# micromouse2019_enc.net
KiCad netlist of a schematic drawn in EAGLE
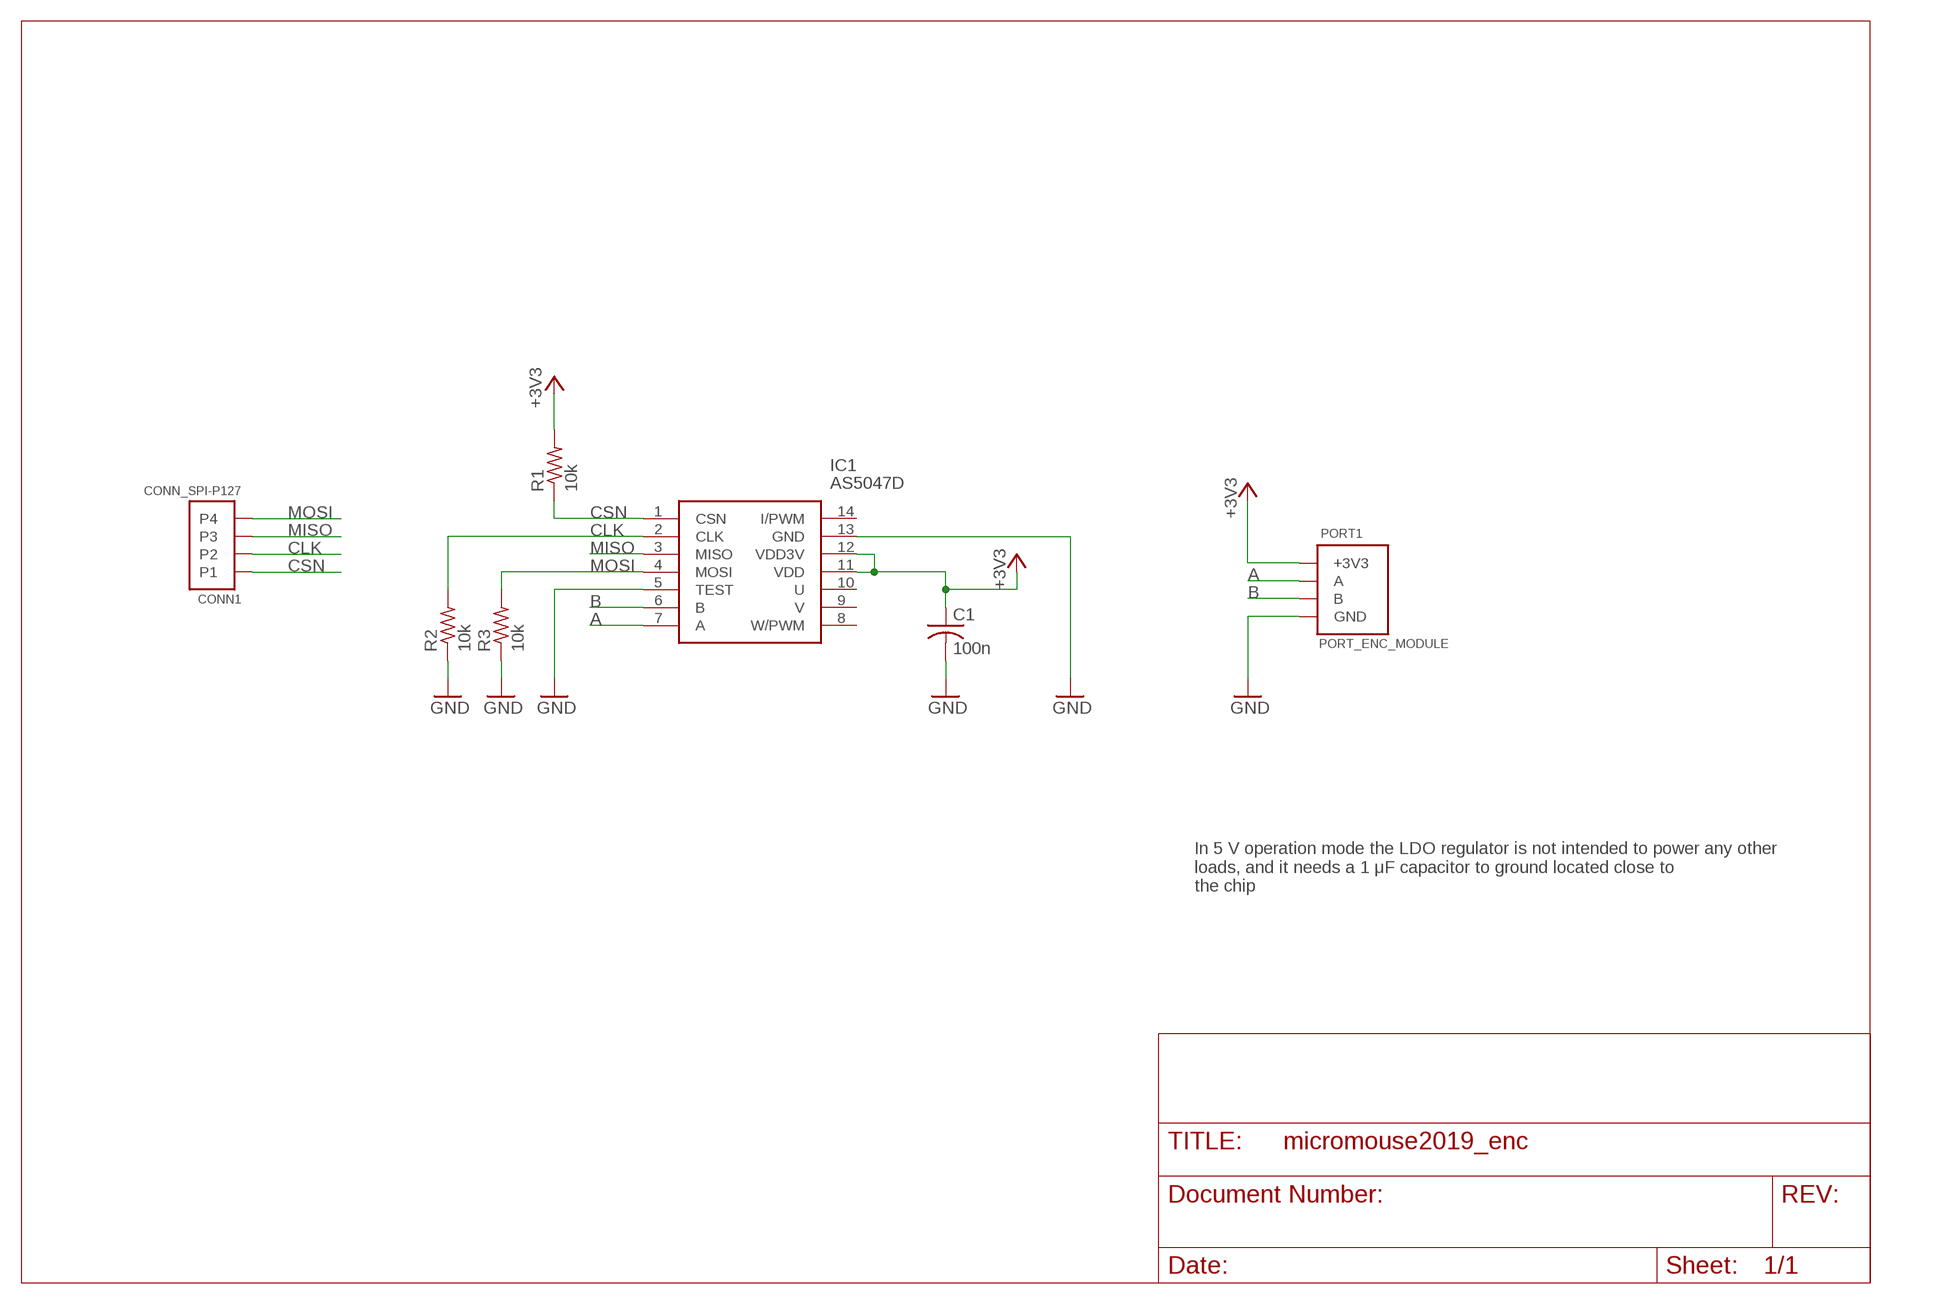
[diagram p0: schematic, sheet 1]

(export (version "E")
  (design (tool "Eeschema 10.0.6"))
  (components
    (comp (ref "C1")
      (value "100n")
      (footprint "eagle-import:C0402")
      (libsource (lib "eagle-import") (part "C-USC0402"))
    )
    (comp (ref "CONN1")
      (value "CONN_SPI-P127")
      (footprint "eagle-import:CONN_SPI_HDRRA4W40P127_1X4_549X220X220B")
      (libsource (lib "eagle-import") (part "CONN_SPI-P127"))
    )
    (comp (ref "IC1")
      (value "AS5047D")
      (footprint "eagle-import:SOP65P640X120-14N")
      (fields
        (field (name "MANUFACTURER_PART_NUMBER") "AS5047D-ATSM")
        (field (name "MOUSER_PART_NUMBER") "985-AS5047D-ATSM")
        (field (name "RS_PART_NUMBER") "1700756")
      )
      (libsource (lib "eagle-import") (part "AS5047D-ATSM"))
    )
    (comp (ref "PORT1")
      (value "PORT_ENC_MODULE")
      (footprint "eagle-import:ENC_PORT_MODULE")
      (libsource (lib "eagle-import") (part "PORT_ENC_MODULE"))
    )
    (comp (ref "R1")
      (value "10k")
      (footprint "eagle-import:R0402")
      (libsource (lib "eagle-import") (part "R-US_R0402"))
    )
    (comp (ref "R2")
      (value "10k")
      (footprint "eagle-import:R0402")
      (libsource (lib "eagle-import") (part "R-US_R0402"))
    )
    (comp (ref "R3")
      (value "10k")
      (footprint "eagle-import:R0402")
      (libsource (lib "eagle-import") (part "R-US_R0402"))
    )
  )
  (nets
    (net (code "1") (name "+3V3") (class "Default")
      (node (ref "C1") (pin "1") (pinfunction "1_1") (pintype "passive"))
      (node (ref "IC1") (pin "11") (pinfunction "VDD_11") (pintype "bidirectional"))
      (node (ref "IC1") (pin "12") (pinfunction "VDD3V_12") (pintype "bidirectional"))
      (node (ref "PORT1") (pin "P3") (pinfunction "+3V3_P3") (pintype "power_in"))
      (node (ref "R1") (pin "2") (pinfunction "2_2") (pintype "passive"))
    )
    (net (code "2") (name "/A") (class "Default")
      (node (ref "IC1") (pin "7") (pinfunction "A_7") (pintype "bidirectional"))
      (node (ref "PORT1") (pin "P1") (pinfunction "A_P1") (pintype "output"))
    )
    (net (code "3") (name "/B") (class "Default")
      (node (ref "IC1") (pin "6") (pinfunction "B_6") (pintype "bidirectional"))
      (node (ref "PORT1") (pin "P2") (pinfunction "B_P2") (pintype "output"))
    )
    (net (code "4") (name "/CLK") (class "Default")
      (node (ref "CONN1") (pin "2") (pinfunction "P2_2") (pintype "bidirectional"))
      (node (ref "IC1") (pin "2") (pinfunction "CLK_2") (pintype "bidirectional"))
      (node (ref "R2") (pin "2") (pinfunction "2_2") (pintype "passive"))
    )
    (net (code "5") (name "/CSN") (class "Default")
      (node (ref "CONN1") (pin "1") (pinfunction "P1_1") (pintype "bidirectional"))
      (node (ref "IC1") (pin "1") (pinfunction "CSN_1") (pintype "bidirectional"))
      (node (ref "R1") (pin "1") (pinfunction "1_1") (pintype "passive"))
    )
    (net (code "6") (name "/MISO") (class "Default")
      (node (ref "CONN1") (pin "3") (pinfunction "P3_3") (pintype "bidirectional"))
      (node (ref "IC1") (pin "3") (pinfunction "MISO_3") (pintype "bidirectional"))
    )
    (net (code "7") (name "/MOSI") (class "Default")
      (node (ref "CONN1") (pin "4") (pinfunction "P4_4") (pintype "bidirectional"))
      (node (ref "IC1") (pin "4") (pinfunction "MOSI_4") (pintype "bidirectional"))
      (node (ref "R3") (pin "2") (pinfunction "2_2") (pintype "passive"))
    )
    (net (code "8") (name "GND") (class "Default")
      (node (ref "C1") (pin "2") (pinfunction "2_2") (pintype "passive"))
      (node (ref "IC1") (pin "13") (pinfunction "GND_13") (pintype "bidirectional"))
      (node (ref "IC1") (pin "5") (pinfunction "TEST_5") (pintype "bidirectional"))
      (node (ref "PORT1") (pin "P4") (pinfunction "GND_P4") (pintype "passive"))
      (node (ref "R2") (pin "1") (pinfunction "1_1") (pintype "passive"))
      (node (ref "R3") (pin "1") (pinfunction "1_1") (pintype "passive"))
    )
    (net (code "9") (name "unconnected-(IC1-I{slash}PWM-Pad14)") (class "Default")
      (node (ref "IC1") (pin "14") (pinfunction "I/PWM_14") (pintype "bidirectional"))
    )
    (net (code "10") (name "unconnected-(IC1-U-Pad10)") (class "Default")
      (node (ref "IC1") (pin "10") (pinfunction "U_10") (pintype "bidirectional"))
    )
    (net (code "11") (name "unconnected-(IC1-V-Pad9)") (class "Default")
      (node (ref "IC1") (pin "9") (pinfunction "V_9") (pintype "bidirectional"))
    )
    (net (code "12") (name "unconnected-(IC1-W{slash}PWM-Pad8)") (class "Default")
      (node (ref "IC1") (pin "8") (pinfunction "W/PWM_8") (pintype "bidirectional"))
    )
  )
)
